# 210806300163-.net
KiCad netlist of a schematic drawn in Altium Designer
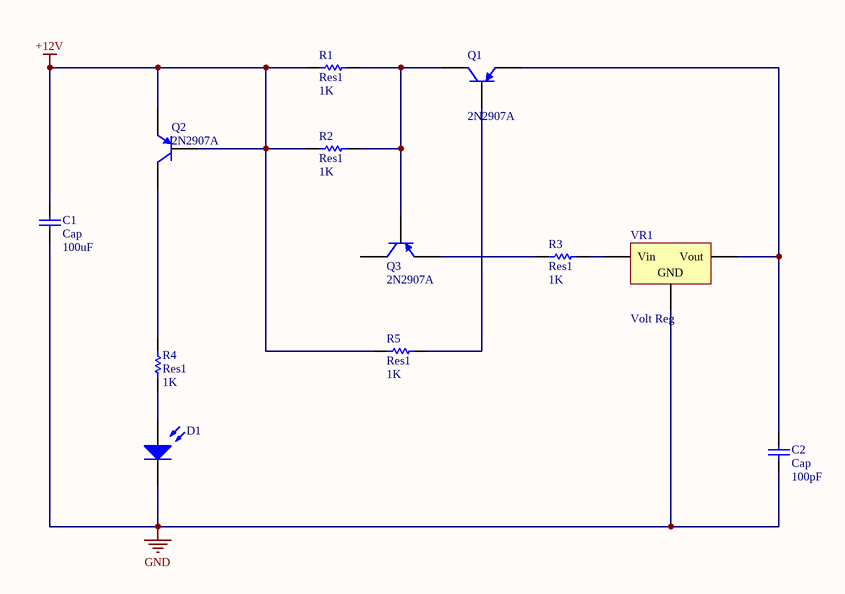
[diagram p0: 210806300163-李烨攀.SchDoc]

(export (version "E")
  (design (tool "Eeschema 10.0.6"))
  (components
    (comp (ref "C1")
      (value "Cap")
      (footprint "RAD-0.3")
      (description "Capacitor")
      (fields (field (name "ALTIUM_VALUE") "100uF") (field (name "PUBLISHER") "Altium Limited"))
      (libsource (lib "Miscellaneous Devices") (part "Cap"))
    )
    (comp (ref "C2")
      (value "Cap")
      (footprint "RAD-0.3")
      (description "Capacitor")
      (fields (field (name "ALTIUM_VALUE") "100pF") (field (name "PUBLISHER") "Altium Limited"))
      (libsource (lib "Miscellaneous Devices") (part "Cap"))
    )
    (comp (ref "D1")
      (value "~")
      (footprint "PIN2")
      (description "Photosensitive Diode")
      (fields (field (name "PUBLISHER") "Altium Limited"))
      (libsource (lib "Miscellaneous Devices") (part "Photo Sen"))
    )
    (comp (ref "Q1")
      (value "2N2907A")
      (footprint "TO-18")
      (description "General Purpose Amplifier and Switch")
      (fields (field (name "PUBLISHER") "Altium Limited"))
      (libsource (lib "ST Discrete BJT") (part "2N2907A"))
    )
    (comp (ref "Q2")
      (value "2N2907A")
      (footprint "TO-18")
      (description "General Purpose Amplifier and Switch")
      (fields (field (name "PUBLISHER") "Altium Limited"))
      (libsource (lib "ST Discrete BJT") (part "2N2907A"))
    )
    (comp (ref "Q3")
      (value "2N2907A")
      (footprint "TO-18")
      (description "General Purpose Amplifier and Switch")
      (fields (field (name "PUBLISHER") "Altium Limited"))
      (libsource (lib "ST Discrete BJT") (part "2N2907A"))
    )
    (comp (ref "R1")
      (value "Res1")
      (footprint "AXIAL-0.3")
      (description "Resistor")
      (fields (field (name "ALTIUM_VALUE") "1K") (field (name "PUBLISHER") "Altium Limited"))
      (libsource (lib "Miscellaneous Devices") (part "Res1"))
    )
    (comp (ref "R2")
      (value "Res1")
      (footprint "AXIAL-0.3")
      (description "Resistor")
      (fields (field (name "ALTIUM_VALUE") "1K") (field (name "PUBLISHER") "Altium Limited"))
      (libsource (lib "Miscellaneous Devices") (part "Res1"))
    )
    (comp (ref "R3")
      (value "Res1")
      (footprint "AXIAL-0.3")
      (description "Resistor")
      (fields (field (name "ALTIUM_VALUE") "1K") (field (name "PUBLISHER") "Altium Limited"))
      (libsource (lib "Miscellaneous Devices") (part "Res1"))
    )
    (comp (ref "R4")
      (value "Res1")
      (footprint "AXIAL-0.3")
      (description "Resistor")
      (fields (field (name "ALTIUM_VALUE") "1K") (field (name "PUBLISHER") "Altium Limited"))
      (libsource (lib "Miscellaneous Devices") (part "Res1"))
    )
    (comp (ref "R5")
      (value "Res1")
      (footprint "AXIAL-0.3")
      (description "Resistor")
      (fields (field (name "ALTIUM_VALUE") "1K") (field (name "PUBLISHER") "Altium Limited"))
      (libsource (lib "Miscellaneous Devices") (part "Res1"))
    )
    (comp (ref "VR1")
      (value "Volt Reg")
      (footprint "TO254P1510-3_4N")
      (description "Voltage Regulator")
      (fields (field (name "PUBLISHER") "Altium Limited"))
      (libsource (lib "Miscellaneous Devices") (part "Volt Reg"))
    )
  )
  (nets
    (net (code "1") (name "+12V") (class "Default")
      (node (ref "C1") (pin "1") (pinfunction "1_1") (pintype "passive"))
      (node (ref "Q2") (pin "1") (pinfunction "B_1") (pintype "passive"))
      (node (ref "Q2") (pin "3") (pinfunction "E_3") (pintype "passive"))
      (node (ref "R1") (pin "1") (pinfunction "1_1") (pintype "passive"))
      (node (ref "R2") (pin "1") (pinfunction "1_1") (pintype "passive"))
      (node (ref "R5") (pin "1") (pinfunction "1_1") (pintype "passive"))
    )
    (net (code "2") (name "GND") (class "Default")
      (node (ref "C1") (pin "2") (pinfunction "2_2") (pintype "passive"))
      (node (ref "C2") (pin "2") (pinfunction "2_2") (pintype "passive"))
      (node (ref "D1") (pin "2") (pinfunction "K_2") (pintype "passive"))
      (node (ref "VR1") (pin "2") (pinfunction "GND_2") (pintype "passive"))
    )
    (net (code "3") (name "Net-(D1-A)") (class "Default")
      (node (ref "D1") (pin "1") (pinfunction "A_1") (pintype "passive"))
      (node (ref "R4") (pin "2") (pinfunction "2_2") (pintype "passive"))
    )
    (net (code "4") (name "Net-(Q1-B)") (class "Default")
      (node (ref "Q1") (pin "1") (pinfunction "B_1") (pintype "passive"))
      (node (ref "R5") (pin "2") (pinfunction "2_2") (pintype "passive"))
    )
    (net (code "5") (name "Net-(Q1-C)") (class "Default")
      (node (ref "Q1") (pin "2") (pinfunction "C_2") (pintype "passive"))
      (node (ref "Q3") (pin "1") (pinfunction "B_1") (pintype "passive"))
      (node (ref "R1") (pin "2") (pinfunction "2_2") (pintype "passive"))
      (node (ref "R2") (pin "2") (pinfunction "2_2") (pintype "passive"))
    )
    (net (code "6") (name "Net-(Q1-E)") (class "Default")
      (node (ref "C2") (pin "1") (pinfunction "1_1") (pintype "passive"))
      (node (ref "Q1") (pin "3") (pinfunction "E_3") (pintype "passive"))
      (node (ref "VR1") (pin "3") (pinfunction "Vout_3") (pintype "passive"))
    )
    (net (code "7") (name "Net-(Q2-C)") (class "Default")
      (node (ref "Q2") (pin "2") (pinfunction "C_2") (pintype "passive"))
      (node (ref "R4") (pin "1") (pinfunction "1_1") (pintype "passive"))
    )
    (net (code "8") (name "Net-(Q3-E)") (class "Default")
      (node (ref "Q3") (pin "3") (pinfunction "E_3") (pintype "passive"))
      (node (ref "R3") (pin "1") (pinfunction "1_1") (pintype "passive"))
    )
    (net (code "9") (name "Net-(VR1-Vin)") (class "Default")
      (node (ref "R3") (pin "2") (pinfunction "2_2") (pintype "passive"))
      (node (ref "VR1") (pin "1") (pinfunction "Vin_1") (pintype "passive"))
    )
    (net (code "10") (name "unconnected-(Q3-C-Pad2)") (class "Default")
      (node (ref "Q3") (pin "2") (pinfunction "C_2") (pintype "passive"))
    )
  )
)
